# 25062016wearable_v1_2_-_routed_99.net
KiCad netlist of a schematic drawn in EAGLE
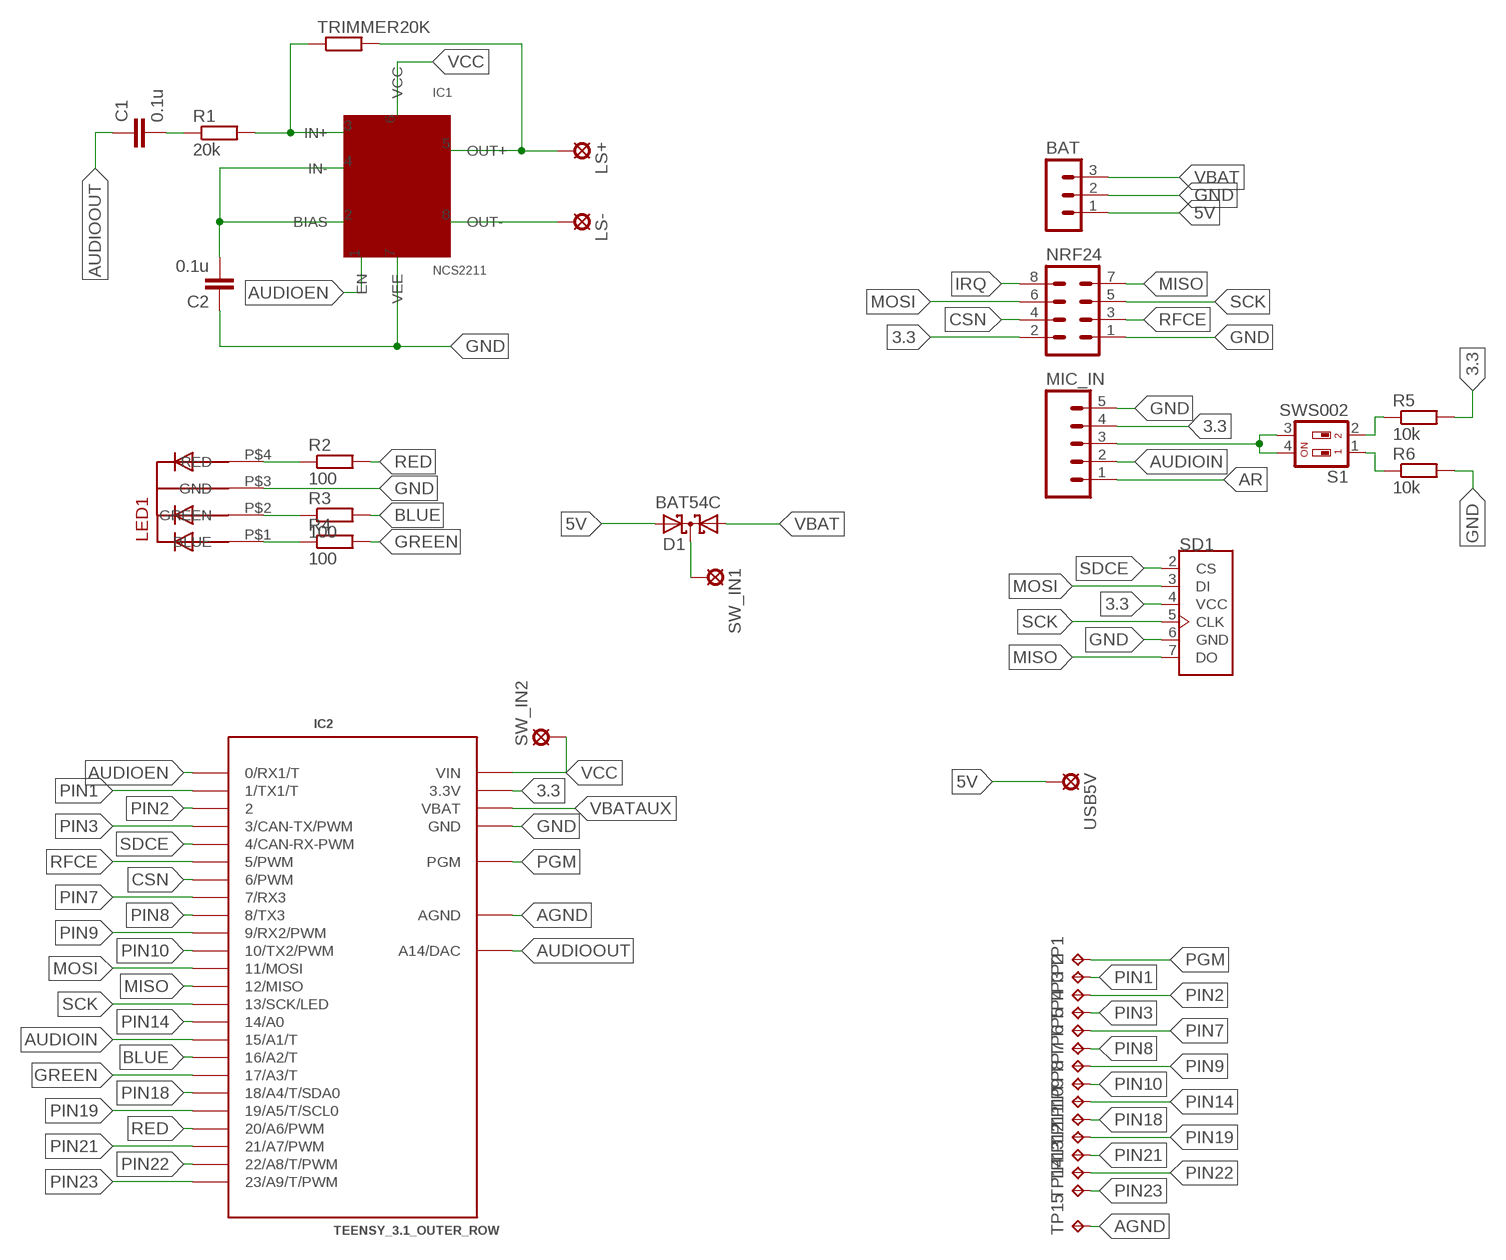
[diagram p0: schematic, sheet 1]

(export (version "E")
  (design (tool "Eeschema 10.0.6"))
  (components
    (comp (ref "BAT")
      (value "MA03-1")
      (footprint "eagle-import:MA03-1")
      (libsource (lib "eagle-import") (part "MA03-1"))
    )
    (comp (ref "C1")
      (value "0.1u")
      (footprint "eagle-import:C2.5-2")
      (libsource (lib "eagle-import") (part "C2.5/2"))
    )
    (comp (ref "C2")
      (value "0.1u")
      (footprint "eagle-import:C2.5-2")
      (libsource (lib "eagle-import") (part "C2.5/2"))
    )
    (comp (ref "D1")
      (value "BAT54C")
      (footprint "eagle-import:SOT23")
      (libsource (lib "eagle-import") (part "BAT54C"))
    )
    (comp (ref "IC1")
      (value "NCS2211")
      (footprint "eagle-import:SOIC-8")
      (libsource (lib "eagle-import") (part "NCS2211"))
    )
    (comp (ref "IC2")
      (value "TEENSY_3.1_OUTER_ROW")
      (footprint "eagle-import:TEENSY3-OUTER_ROW")
      (libsource (lib "eagle-import") (part "TEENSY_3.1_OUTER_ROW"))
    )
    (comp (ref "LED1")
      (value "5MMRGBLED")
      (footprint "eagle-import:LED5MMRGB")
      (libsource (lib "eagle-import") (part "5MMRGBLED"))
    )
    (comp (ref "LS+")
      (value "LSP10")
      (footprint "eagle-import:LSP10")
      (libsource (lib "eagle-import") (part "LSP10"))
    )
    (comp (ref "LS-")
      (value "LSP10")
      (footprint "eagle-import:LSP10")
      (libsource (lib "eagle-import") (part "LSP10"))
    )
    (comp (ref "MIC_IN")
      (value "MA05")
      (footprint "eagle-import:05PA")
      (libsource (lib "eagle-import") (part "MA05"))
    )
    (comp (ref "NRF24")
      (value "MA04-2")
      (footprint "eagle-import:MA04-2")
      (libsource (lib "eagle-import") (part "MA04-2"))
    )
    (comp (ref "R1")
      (value "20k")
      (footprint "eagle-import:0204_7")
      (libsource (lib "eagle-import") (part "R-EU_0204/7"))
    )
    (comp (ref "R2")
      (value "100")
      (footprint "eagle-import:0207_2V")
      (libsource (lib "eagle-import") (part "R-EU_0207/2V"))
    )
    (comp (ref "R3")
      (value "100")
      (footprint "eagle-import:0207_2V")
      (libsource (lib "eagle-import") (part "R-EU_0207/2V"))
    )
    (comp (ref "R4")
      (value "100")
      (footprint "eagle-import:0207_2V")
      (libsource (lib "eagle-import") (part "R-EU_0207/2V"))
    )
    (comp (ref "R5")
      (value "10k")
      (footprint "eagle-import:0207_2V")
      (libsource (lib "eagle-import") (part "R-EU_0207/2V"))
    )
    (comp (ref "R6")
      (value "10k")
      (footprint "eagle-import:0207_2V")
      (libsource (lib "eagle-import") (part "R-EU_0207/2V"))
    )
    (comp (ref "S1")
      (value "SWS002")
      (footprint "eagle-import:SMS-002")
      (libsource (lib "eagle-import") (part "SWS002"))
    )
    (comp (ref "SD1")
      (value "MICROSD_SF-MICROSD")
      (footprint "eagle-import:MICROSD_MICROSD")
      (libsource (lib "eagle-import") (part "MICROSD_SF-MICROSD"))
    )
    (comp (ref "SW_IN1")
      (value "SE11")
      (footprint "eagle-import:SE11")
      (libsource (lib "eagle-import") (part "SE11"))
    )
    (comp (ref "SW_IN2")
      (value "SE11")
      (footprint "eagle-import:SE11")
      (libsource (lib "eagle-import") (part "SE11"))
    )
    (comp (ref "TP1")
      (value "TPPAD1-13")
      (footprint "eagle-import:P1-13")
      (libsource (lib "eagle-import") (part "TPPAD1-13"))
    )
    (comp (ref "TP2")
      (value "TPPAD1-13")
      (footprint "eagle-import:P1-13")
      (libsource (lib "eagle-import") (part "TPPAD1-13"))
    )
    (comp (ref "TP3")
      (value "TPPAD1-13")
      (footprint "eagle-import:P1-13")
      (libsource (lib "eagle-import") (part "TPPAD1-13"))
    )
    (comp (ref "TP4")
      (value "TPPAD1-13")
      (footprint "eagle-import:P1-13")
      (libsource (lib "eagle-import") (part "TPPAD1-13"))
    )
    (comp (ref "TP5")
      (value "TPPAD1-13")
      (footprint "eagle-import:P1-13")
      (libsource (lib "eagle-import") (part "TPPAD1-13"))
    )
    (comp (ref "TP6")
      (value "TPPAD1-13")
      (footprint "eagle-import:P1-13")
      (libsource (lib "eagle-import") (part "TPPAD1-13"))
    )
    (comp (ref "TP7")
      (value "TPPAD1-13")
      (footprint "eagle-import:P1-13")
      (libsource (lib "eagle-import") (part "TPPAD1-13"))
    )
    (comp (ref "TP8")
      (value "TPPAD1-13")
      (footprint "eagle-import:P1-13")
      (libsource (lib "eagle-import") (part "TPPAD1-13"))
    )
    (comp (ref "TP9")
      (value "TPPAD1-13")
      (footprint "eagle-import:P1-13")
      (libsource (lib "eagle-import") (part "TPPAD1-13"))
    )
    (comp (ref "TP10")
      (value "TPPAD1-13")
      (footprint "eagle-import:P1-13")
      (libsource (lib "eagle-import") (part "TPPAD1-13"))
    )
    (comp (ref "TP11")
      (value "TPPAD1-13")
      (footprint "eagle-import:P1-13")
      (libsource (lib "eagle-import") (part "TPPAD1-13"))
    )
    (comp (ref "TP12")
      (value "TPPAD1-13")
      (footprint "eagle-import:P1-13")
      (libsource (lib "eagle-import") (part "TPPAD1-13"))
    )
    (comp (ref "TP13")
      (value "TPPAD1-13")
      (footprint "eagle-import:P1-13")
      (libsource (lib "eagle-import") (part "TPPAD1-13"))
    )
    (comp (ref "TP14")
      (value "TPPAD1-13")
      (footprint "eagle-import:P1-13")
      (libsource (lib "eagle-import") (part "TPPAD1-13"))
    )
    (comp (ref "TP15")
      (value "TPPAD1-13")
      (footprint "eagle-import:P1-13")
      (libsource (lib "eagle-import") (part "TPPAD1-13"))
    )
    (comp (ref "TRIMMER20K")
      (value "R-EU_0207/2V")
      (footprint "eagle-import:0207_2V")
      (libsource (lib "eagle-import") (part "R-EU_0207/2V"))
    )
    (comp (ref "USB5V")
      (value "LSP10")
      (footprint "eagle-import:LSP10")
      (libsource (lib "eagle-import") (part "LSP10"))
    )
  )
  (nets
    (net (code "1") (name "3.3") (class "Default")
      (node (ref "IC2") (pin "3.3V") (pinfunction "3.3V_3.3V") (pintype "power_in"))
      (node (ref "IC2") (pin "3.3V1") (pinfunction "3.3V_3.3V1") (pintype "power_in"))
      (node (ref "MIC_IN") (pin "4") (pinfunction "4_4") (pintype "passive"))
      (node (ref "NRF24") (pin "2") (pinfunction "2_2") (pintype "passive"))
      (node (ref "R5") (pin "2") (pinfunction "2_2") (pintype "passive"))
      (node (ref "SD1") (pin "4") (pinfunction "VCC_4") (pintype "power_in"))
    )
    (net (code "2") (name "5V") (class "Default")
      (node (ref "BAT") (pin "1") (pinfunction "1_1") (pintype "passive"))
      (node (ref "D1") (pin "2") (pinfunction "A2_2") (pintype "passive"))
      (node (ref "USB5V") (pin "MP") (pinfunction "MP_MP") (pintype "passive"))
    )
    (net (code "3") (name "AGND") (class "Default")
      (node (ref "IC2") (pin "AGND") (pinfunction "AGND_AGND") (pintype "power_in"))
      (node (ref "TP15") (pin "TP") (pinfunction "TP_TP") (pintype "input"))
    )
    (net (code "4") (name "AR") (class "Default")
      (node (ref "MIC_IN") (pin "1") (pinfunction "1_1") (pintype "passive"))
    )
    (net (code "5") (name "AUDIOEN") (class "Default")
      (node (ref "IC1") (pin "1") (pinfunction "EN_1") (pintype "bidirectional"))
      (node (ref "IC2") (pin "0") (pinfunction "0/RX1/T_0") (pintype "bidirectional"))
    )
    (net (code "6") (name "AUDIOIN") (class "Default")
      (node (ref "IC2") (pin "15/A1") (pinfunction "15/A1/T_15/A1") (pintype "bidirectional"))
      (node (ref "MIC_IN") (pin "2") (pinfunction "2_2") (pintype "passive"))
    )
    (net (code "7") (name "AUDIOOUT") (class "Default")
      (node (ref "C1") (pin "1") (pinfunction "1_1") (pintype "passive"))
      (node (ref "IC2") (pin "RESET/DAC") (pinfunction "A14/DAC_RESET/DAC") (pintype "bidirectional"))
    )
    (net (code "8") (name "BLUE") (class "Default")
      (node (ref "IC2") (pin "16/A2") (pinfunction "16/A2/T_16/A2") (pintype "bidirectional"))
      (node (ref "R3") (pin "2") (pinfunction "2_2") (pintype "passive"))
    )
    (net (code "9") (name "CSN") (class "Default")
      (node (ref "IC2") (pin "6") (pinfunction "6/PWM_6") (pintype "bidirectional"))
      (node (ref "NRF24") (pin "4") (pinfunction "4_4") (pintype "passive"))
    )
    (net (code "10") (name "GND") (class "Default")
      (node (ref "BAT") (pin "2") (pinfunction "2_2") (pintype "passive"))
      (node (ref "C2") (pin "1") (pinfunction "1_1") (pintype "passive"))
      (node (ref "IC1") (pin "7") (pinfunction "VEE_7") (pintype "bidirectional"))
      (node (ref "IC2") (pin "GND") (pinfunction "GND_GND") (pintype "power_in"))
      (node (ref "IC2") (pin "GND1") (pinfunction "GND_GND1") (pintype "power_in"))
      (node (ref "LED1") (pin "P$3") (pinfunction "GND_P$3") (pintype "bidirectional"))
      (node (ref "MIC_IN") (pin "5") (pinfunction "5_5") (pintype "passive"))
      (node (ref "NRF24") (pin "1") (pinfunction "1_1") (pintype "passive"))
      (node (ref "R6") (pin "2") (pinfunction "2_2") (pintype "passive"))
      (node (ref "SD1") (pin "6") (pinfunction "GND_6") (pintype "power_in"))
    )
    (net (code "11") (name "GREEN") (class "Default")
      (node (ref "IC2") (pin "17/A3") (pinfunction "17/A3/T_17/A3") (pintype "bidirectional"))
      (node (ref "R4") (pin "2") (pinfunction "2_2") (pintype "passive"))
    )
    (net (code "12") (name "IRQ") (class "Default")
      (node (ref "NRF24") (pin "8") (pinfunction "8_8") (pintype "passive"))
    )
    (net (code "13") (name "MISO") (class "Default")
      (node (ref "IC2") (pin "12") (pinfunction "12/MISO_12") (pintype "bidirectional"))
      (node (ref "NRF24") (pin "7") (pinfunction "7_7") (pintype "passive"))
      (node (ref "SD1") (pin "7") (pinfunction "DO_7") (pintype "output"))
    )
    (net (code "14") (name "MOSI") (class "Default")
      (node (ref "IC2") (pin "11") (pinfunction "11/MOSI_11") (pintype "bidirectional"))
      (node (ref "NRF24") (pin "6") (pinfunction "6_6") (pintype "passive"))
      (node (ref "SD1") (pin "3") (pinfunction "DI_3") (pintype "input"))
    )
    (net (code "15") (name "Net-(C1-Pad2)") (class "Default")
      (node (ref "C1") (pin "2") (pinfunction "2_2") (pintype "passive"))
      (node (ref "R1") (pin "1") (pinfunction "1_1") (pintype "passive"))
    )
    (net (code "16") (name "Net-(D1-CC)") (class "Default")
      (node (ref "D1") (pin "3") (pinfunction "CC_3") (pintype "passive"))
      (node (ref "SW_IN1") (pin "MP") (pinfunction "MP_MP") (pintype "passive"))
    )
    (net (code "17") (name "Net-(IC1-BIAS)") (class "Default")
      (node (ref "C2") (pin "2") (pinfunction "2_2") (pintype "passive"))
      (node (ref "IC1") (pin "2") (pinfunction "BIAS_2") (pintype "bidirectional"))
      (node (ref "IC1") (pin "4") (pinfunction "IN-_4") (pintype "bidirectional"))
    )
    (net (code "18") (name "Net-(IC1-IN+)") (class "Default")
      (node (ref "IC1") (pin "3") (pinfunction "IN+_3") (pintype "bidirectional"))
      (node (ref "R1") (pin "2") (pinfunction "2_2") (pintype "passive"))
      (node (ref "TRIMMER20K") (pin "1") (pinfunction "1_1") (pintype "passive"))
    )
    (net (code "19") (name "Net-(IC1-OUT+)") (class "Default")
      (node (ref "IC1") (pin "5") (pinfunction "OUT+_5") (pintype "bidirectional"))
      (node (ref "LS+") (pin "MP") (pinfunction "MP_MP") (pintype "passive"))
      (node (ref "TRIMMER20K") (pin "2") (pinfunction "2_2") (pintype "passive"))
    )
    (net (code "20") (name "Net-(IC1-OUT-)") (class "Default")
      (node (ref "IC1") (pin "8") (pinfunction "OUT-_8") (pintype "bidirectional"))
      (node (ref "LS-") (pin "MP") (pinfunction "MP_MP") (pintype "passive"))
    )
    (net (code "21") (name "Net-(LED1-BLUE)") (class "Default")
      (node (ref "LED1") (pin "P$1") (pinfunction "BLUE_P$1") (pintype "bidirectional"))
      (node (ref "R4") (pin "1") (pinfunction "1_1") (pintype "passive"))
    )
    (net (code "22") (name "Net-(LED1-GREEN)") (class "Default")
      (node (ref "LED1") (pin "P$2") (pinfunction "GREEN_P$2") (pintype "bidirectional"))
      (node (ref "R3") (pin "1") (pinfunction "1_1") (pintype "passive"))
    )
    (net (code "23") (name "Net-(LED1-RED)") (class "Default")
      (node (ref "LED1") (pin "P$4") (pinfunction "RED_P$4") (pintype "bidirectional"))
      (node (ref "R2") (pin "1") (pinfunction "1_1") (pintype "passive"))
    )
    (net (code "24") (name "Net-(MIC_IN-Pad3)") (class "Default")
      (node (ref "MIC_IN") (pin "3") (pinfunction "3_3") (pintype "passive"))
      (node (ref "S1") (pin "3") (pinfunction "3_3") (pintype "passive"))
      (node (ref "S1") (pin "4") (pinfunction "4_4") (pintype "passive"))
    )
    (net (code "25") (name "Net-(R5-Pad1)") (class "Default")
      (node (ref "R5") (pin "1") (pinfunction "1_1") (pintype "passive"))
      (node (ref "S1") (pin "2") (pinfunction "2_2") (pintype "passive"))
    )
    (net (code "26") (name "Net-(R6-Pad1)") (class "Default")
      (node (ref "R6") (pin "1") (pinfunction "1_1") (pintype "passive"))
      (node (ref "S1") (pin "1") (pinfunction "1_1") (pintype "passive"))
    )
    (net (code "27") (name "PGM") (class "Default")
      (node (ref "IC2") (pin "PGM") (pinfunction "PGM_PGM") (pintype "bidirectional"))
      (node (ref "TP1") (pin "TP") (pinfunction "TP_TP") (pintype "input"))
    )
    (net (code "28") (name "PIN1") (class "Default")
      (node (ref "IC2") (pin "1") (pinfunction "1/TX1/T_1") (pintype "bidirectional"))
      (node (ref "TP2") (pin "TP") (pinfunction "TP_TP") (pintype "input"))
    )
    (net (code "29") (name "PIN2") (class "Default")
      (node (ref "IC2") (pin "2") (pinfunction "2_2") (pintype "bidirectional"))
      (node (ref "TP3") (pin "TP") (pinfunction "TP_TP") (pintype "input"))
    )
    (net (code "30") (name "PIN3") (class "Default")
      (node (ref "IC2") (pin "3") (pinfunction "3/CAN-TX/PWM_3") (pintype "bidirectional"))
      (node (ref "TP4") (pin "TP") (pinfunction "TP_TP") (pintype "input"))
    )
    (net (code "31") (name "PIN7") (class "Default")
      (node (ref "IC2") (pin "7") (pinfunction "7/RX3_7") (pintype "bidirectional"))
      (node (ref "TP5") (pin "TP") (pinfunction "TP_TP") (pintype "input"))
    )
    (net (code "32") (name "PIN8") (class "Default")
      (node (ref "IC2") (pin "8") (pinfunction "8/TX3_8") (pintype "bidirectional"))
      (node (ref "TP6") (pin "TP") (pinfunction "TP_TP") (pintype "input"))
    )
    (net (code "33") (name "PIN9") (class "Default")
      (node (ref "IC2") (pin "9") (pinfunction "9/RX2/PWM_9") (pintype "bidirectional"))
      (node (ref "TP7") (pin "TP") (pinfunction "TP_TP") (pintype "input"))
    )
    (net (code "34") (name "PIN10") (class "Default")
      (node (ref "IC2") (pin "10") (pinfunction "10/TX2/PWM_10") (pintype "bidirectional"))
      (node (ref "TP8") (pin "TP") (pinfunction "TP_TP") (pintype "input"))
    )
    (net (code "35") (name "PIN14") (class "Default")
      (node (ref "IC2") (pin "14/A0") (pinfunction "14/A0_14/A0") (pintype "bidirectional"))
      (node (ref "TP9") (pin "TP") (pinfunction "TP_TP") (pintype "input"))
    )
    (net (code "36") (name "PIN18") (class "Default")
      (node (ref "IC2") (pin "18/A4") (pinfunction "18/A4/T/SDA0_18/A4") (pintype "bidirectional"))
      (node (ref "TP10") (pin "TP") (pinfunction "TP_TP") (pintype "input"))
    )
    (net (code "37") (name "PIN19") (class "Default")
      (node (ref "IC2") (pin "19/A5") (pinfunction "19/A5/T/SCL0_19/A5") (pintype "bidirectional"))
      (node (ref "TP11") (pin "TP") (pinfunction "TP_TP") (pintype "input"))
    )
    (net (code "38") (name "PIN21") (class "Default")
      (node (ref "IC2") (pin "21/A7") (pinfunction "21/A7/PWM_21/A7") (pintype "bidirectional"))
      (node (ref "TP12") (pin "TP") (pinfunction "TP_TP") (pintype "input"))
    )
    (net (code "39") (name "PIN22") (class "Default")
      (node (ref "IC2") (pin "22/A8") (pinfunction "22/A8/T/PWM_22/A8") (pintype "bidirectional"))
      (node (ref "TP13") (pin "TP") (pinfunction "TP_TP") (pintype "input"))
    )
    (net (code "40") (name "PIN23") (class "Default")
      (node (ref "IC2") (pin "23/A9") (pinfunction "23/A9/T/PWM_23/A9") (pintype "bidirectional"))
      (node (ref "TP14") (pin "TP") (pinfunction "TP_TP") (pintype "input"))
    )
    (net (code "41") (name "RED") (class "Default")
      (node (ref "IC2") (pin "20/A6") (pinfunction "20/A6/PWM_20/A6") (pintype "bidirectional"))
      (node (ref "R2") (pin "2") (pinfunction "2_2") (pintype "passive"))
    )
    (net (code "42") (name "RFCE") (class "Default")
      (node (ref "IC2") (pin "5") (pinfunction "5/PWM_5") (pintype "bidirectional"))
      (node (ref "NRF24") (pin "3") (pinfunction "3_3") (pintype "passive"))
    )
    (net (code "43") (name "SCK") (class "Default")
      (node (ref "IC2") (pin "13") (pinfunction "13/SCK/LED_13") (pintype "bidirectional"))
      (node (ref "NRF24") (pin "5") (pinfunction "5_5") (pintype "passive"))
      (node (ref "SD1") (pin "5") (pinfunction "CLK_5") (pintype "input"))
    )
    (net (code "44") (name "SDCE") (class "Default")
      (node (ref "IC2") (pin "4") (pinfunction "4/CAN-RX-PWM_4") (pintype "bidirectional"))
      (node (ref "SD1") (pin "2") (pinfunction "CS_2") (pintype "input"))
    )
    (net (code "45") (name "VBAT") (class "Default")
      (node (ref "BAT") (pin "3") (pinfunction "3_3") (pintype "passive"))
      (node (ref "D1") (pin "1") (pinfunction "A1_1") (pintype "passive"))
    )
    (net (code "46") (name "VBATAUX") (class "Default")
      (node (ref "IC2") (pin "VBAT") (pinfunction "VBAT_VBAT") (pintype "power_in"))
    )
    (net (code "47") (name "VCC") (class "Default")
      (node (ref "IC1") (pin "6") (pinfunction "VCC_6") (pintype "bidirectional"))
      (node (ref "IC2") (pin "VIN") (pinfunction "VIN_VIN") (pintype "power_in"))
      (node (ref "SW_IN2") (pin "MP") (pinfunction "MP_MP") (pintype "passive"))
    )
  )
)
